# 2024-ZT-2.net
KiCad netlist of a schematic drawn in EasyEDA Pro
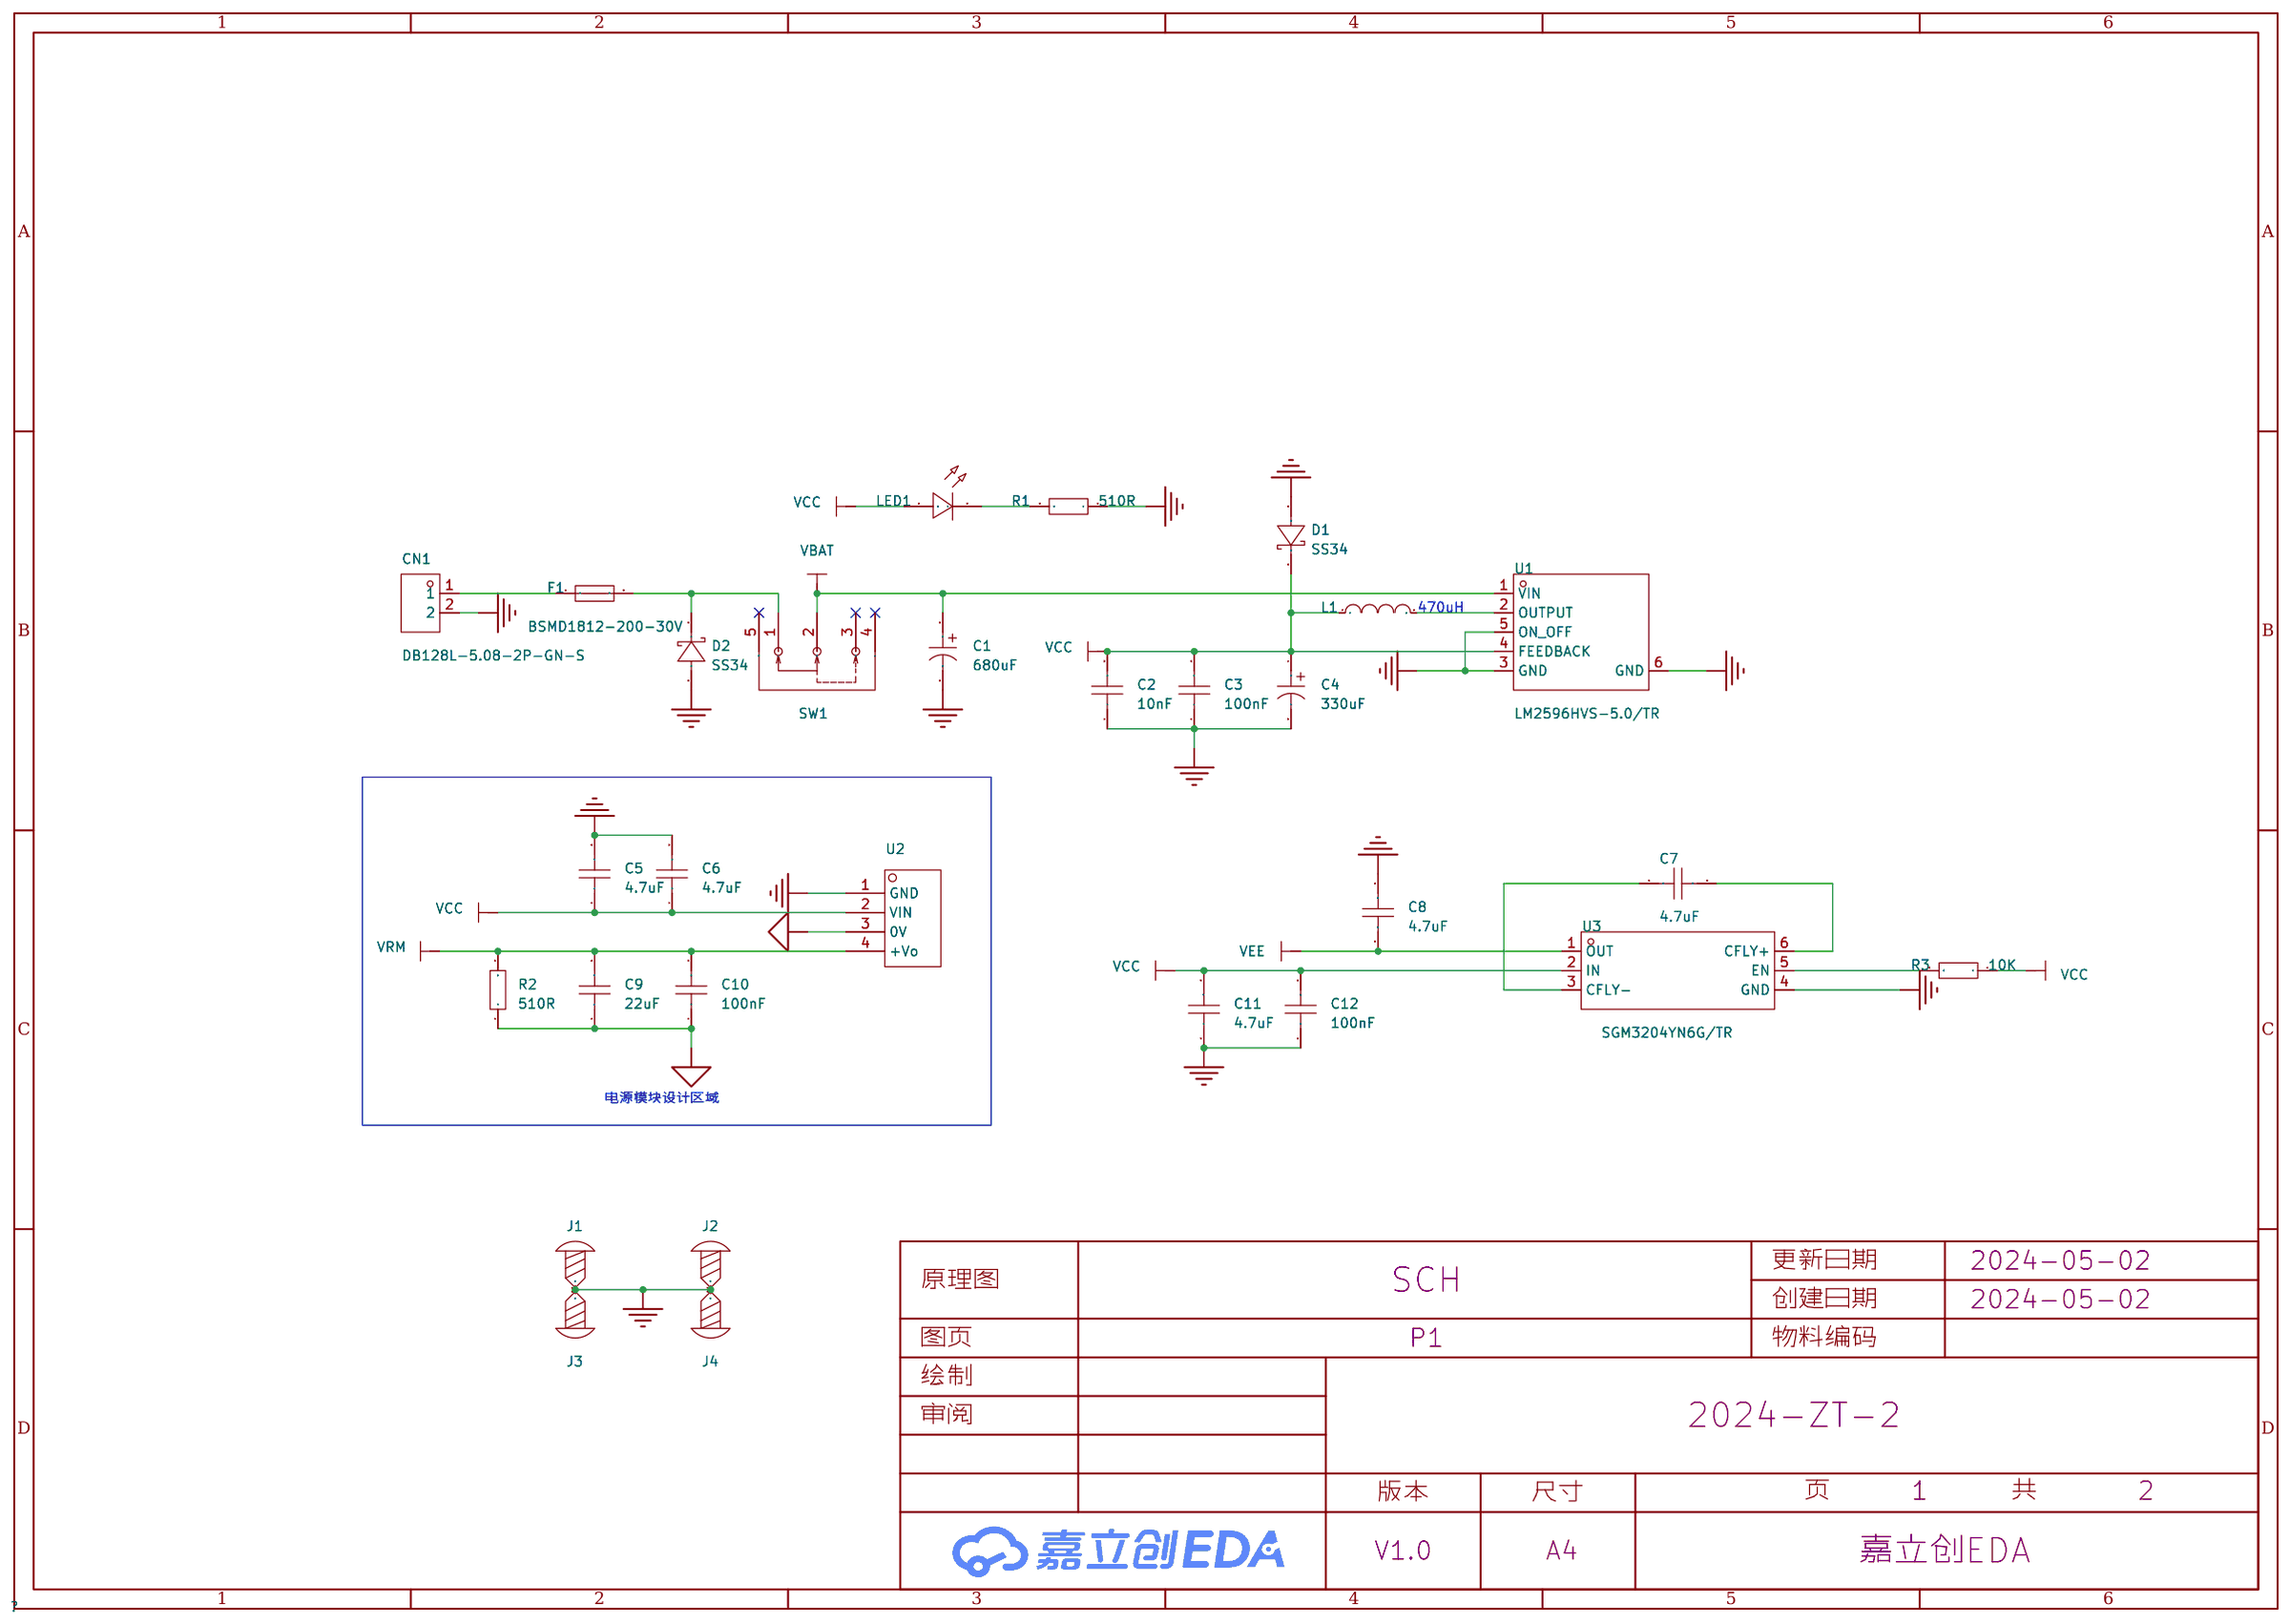
[diagram p0: P1]
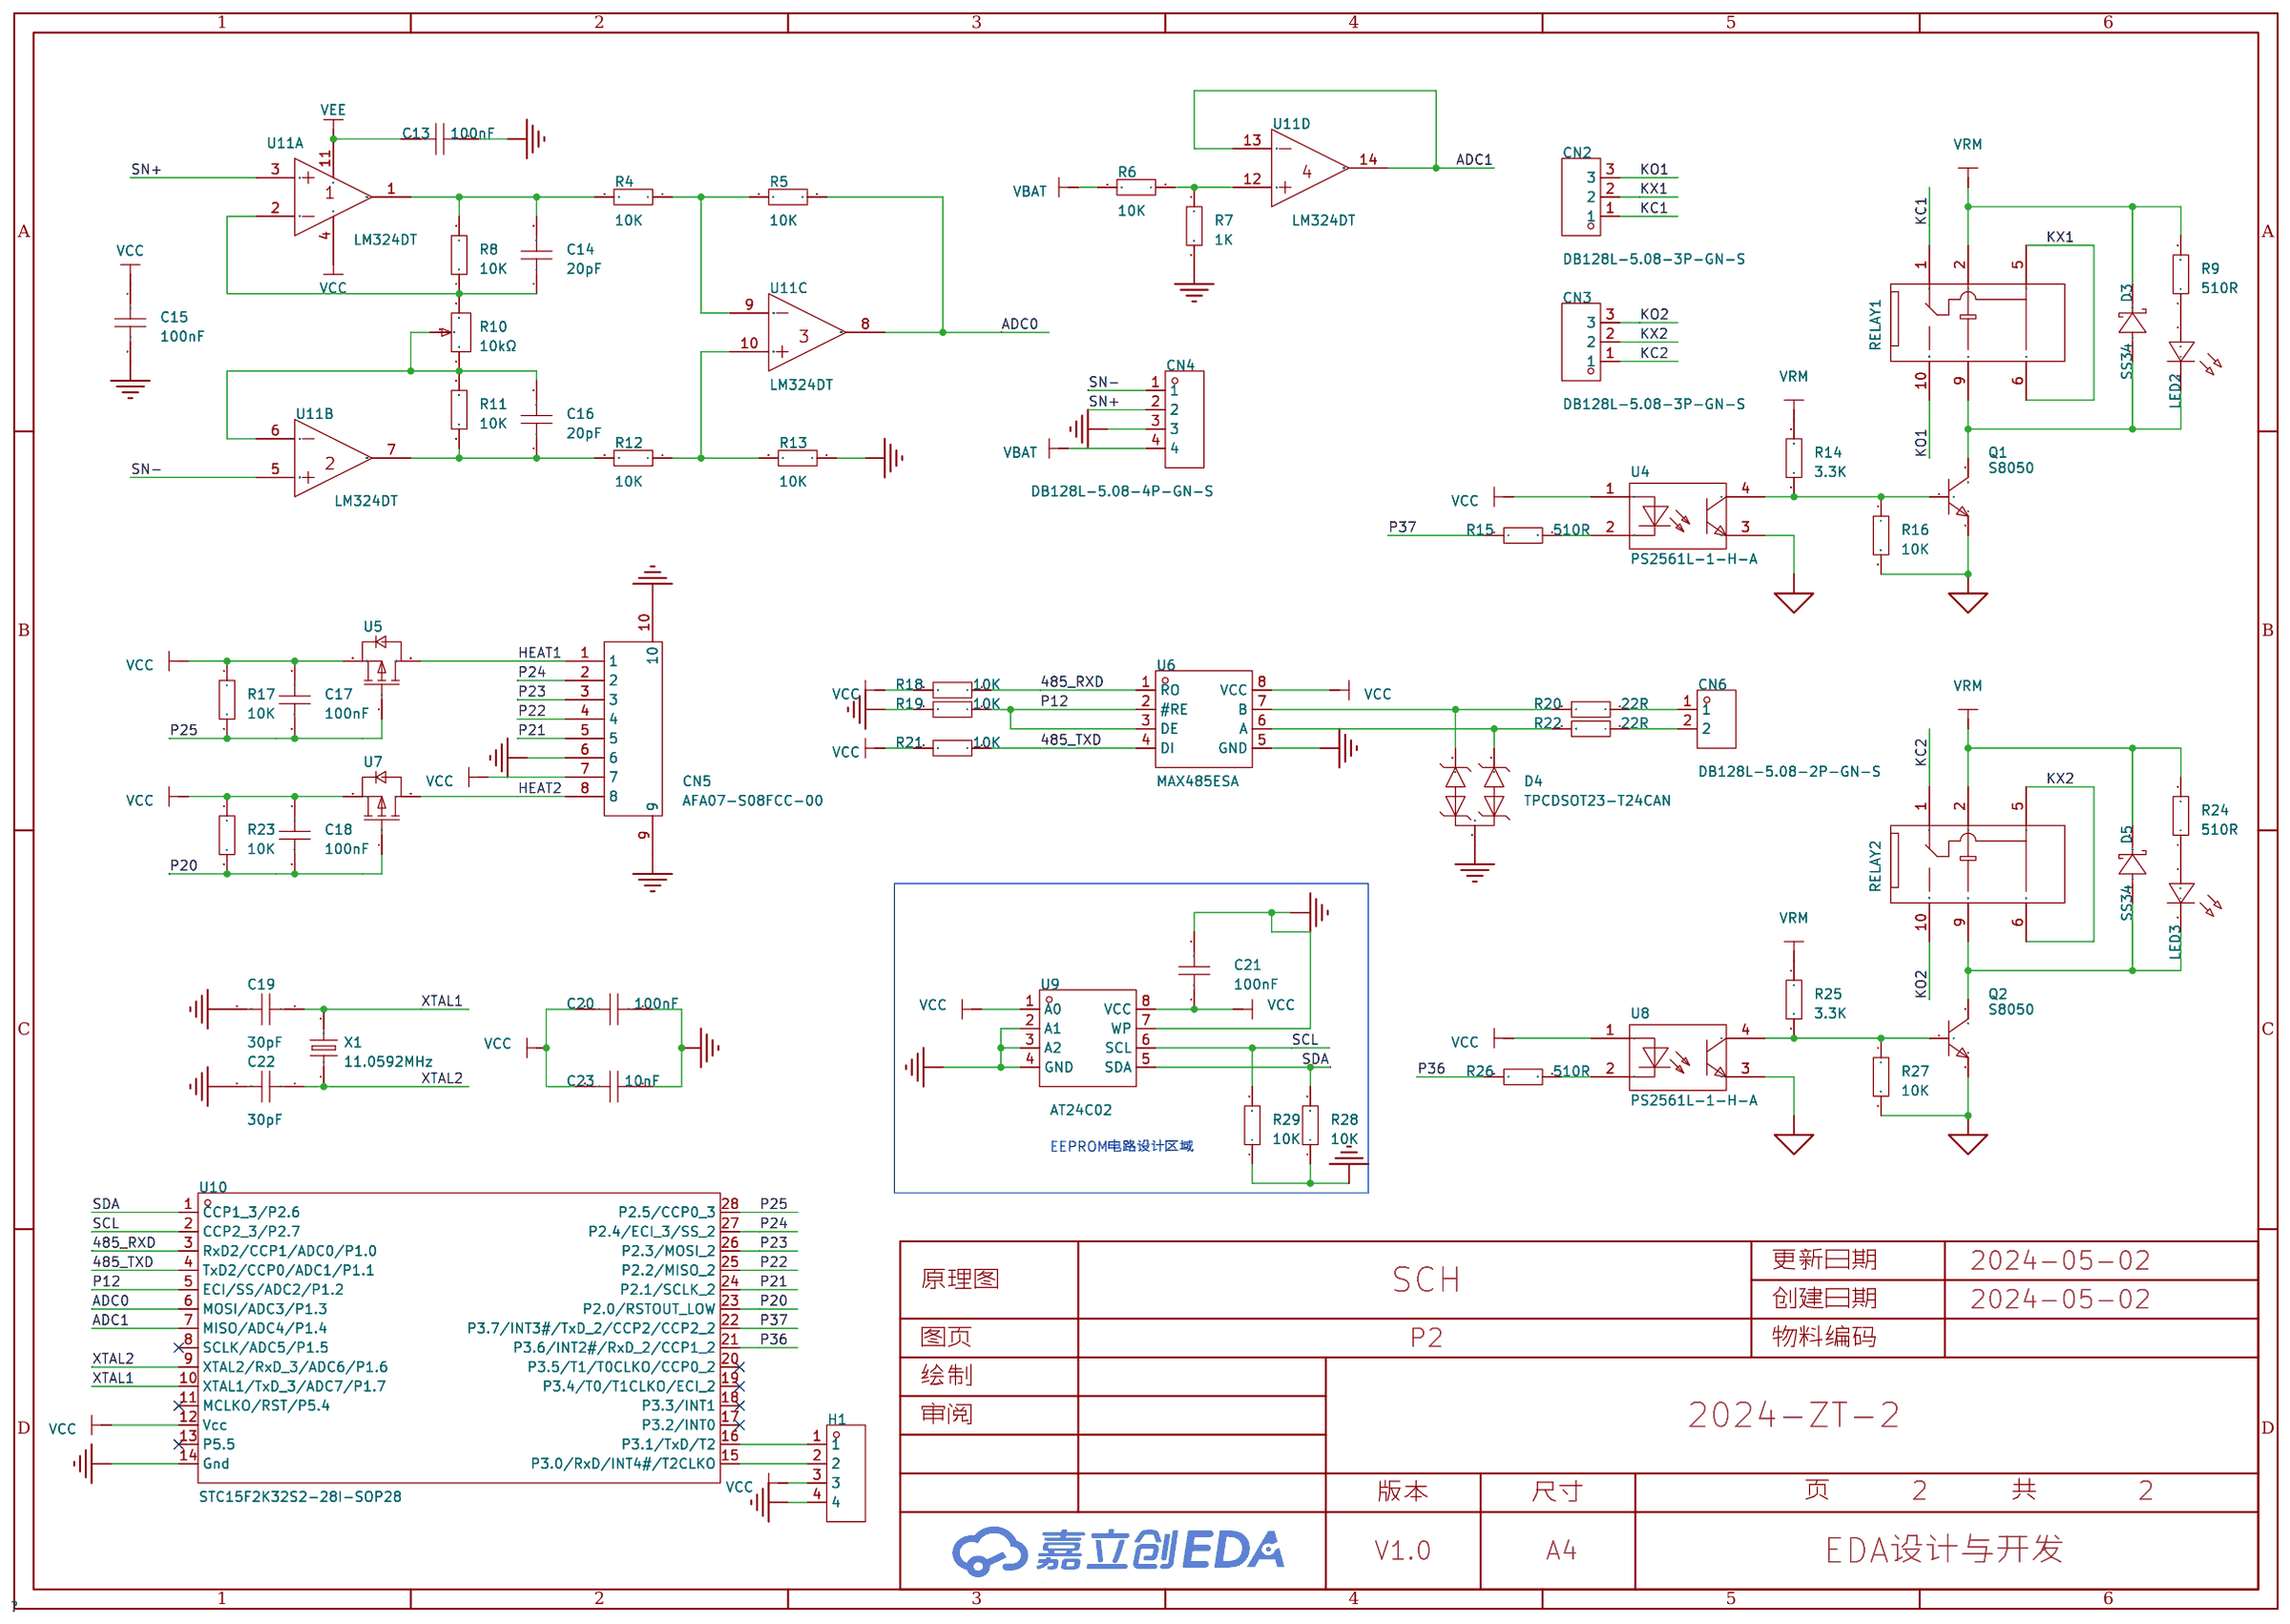
[diagram p1: P2]

(export (version "E")
  (design (tool "Eeschema 10.0.6"))
  (components
    (comp (ref "C1")
      (value "680uF")
      (footprint "easyedapro:CAP-SMD_BD10.0-L10.3-W10.3-LS11.3-FD")
      (description "容值:680uF;精度:±20%;额定电压:35V;纹波电流:380mA;")
      (fields (field (name "Manufacturer Part") "126RV0105") (field (name "Manufacturer") "KNSCHA(科尼盛)"))
      (libsource (lib "easyedapro") (part "126RV0105"))
    )
    (comp (ref "C2")
      (value "10nF")
      (footprint "easyedapro:C0805")
      (libsource (lib "easyedapro") (part "CapAcitance"))
    )
    (comp (ref "C3")
      (value "100nF")
      (footprint "easyedapro:C0805")
      (libsource (lib "easyedapro") (part "CapAcitance"))
    )
    (comp (ref "C4")
      (value "330uF")
      (footprint "easyedapro:CAP-SMD_BD6.3-L6.6-W6.6-LS7.6-RD")
      (description "容值:330uF;精度:±20%;额定电压:16V;纹波电流:170mA;")
      (fields (field (name "Manufacturer Part") "126RV0107") (field (name "Manufacturer") "KNSCHA(科尼盛)"))
      (libsource (lib "easyedapro") (part "126RV0107"))
    )
    (comp (ref "C5")
      (value "4.7uF")
      (footprint "easyedapro:C1206")
      (description "容值:22uF;精度:±10%;额定电压:16V;材质(温度系数):X5R;")
      (fields
        (field (name "Manufacturer Part") "CL31A226KOHNNNE")
        (field (name "Manufacturer") "SAMSUNG(三星)")
      )
      (libsource (lib "easyedapro") (part "CL31A226KOHNNNE"))
    )
    (comp (ref "C6")
      (value "4.7uF")
      (footprint "easyedapro:C1206")
      (description "容值:22uF;精度:±10%;额定电压:16V;材质(温度系数):X5R;")
      (fields
        (field (name "Manufacturer Part") "CL31A226KOHNNNE")
        (field (name "Manufacturer") "SAMSUNG(三星)")
      )
      (libsource (lib "easyedapro") (part "CL31A226KOHNNNE"))
    )
    (comp (ref "C7")
      (value "4.7uF")
      (footprint "easyedapro:C1206")
      (description "容值:22uF;精度:±10%;额定电压:16V;材质(温度系数):X5R;")
      (fields
        (field (name "Manufacturer Part") "CL31A226KOHNNNE")
        (field (name "Manufacturer") "SAMSUNG(三星)")
      )
      (libsource (lib "easyedapro") (part "CL31A226KOHNNNE"))
    )
    (comp (ref "C8")
      (value "4.7uF")
      (footprint "easyedapro:C1206")
      (description "容值:22uF;精度:±10%;额定电压:16V;材质(温度系数):X5R;")
      (fields
        (field (name "Manufacturer Part") "CL31A226KOHNNNE")
        (field (name "Manufacturer") "SAMSUNG(三星)")
      )
      (libsource (lib "easyedapro") (part "CL31A226KOHNNNE"))
    )
    (comp (ref "C9")
      (value "22uF")
      (footprint "easyedapro:C1206")
      (description "容值:22uF;精度:±10%;额定电压:16V;材质(温度系数):X5R;")
      (fields
        (field (name "Manufacturer Part") "CL31A226KOHNNNE")
        (field (name "Manufacturer") "SAMSUNG(三星)")
      )
      (libsource (lib "easyedapro") (part "CL31A226KOHNNNE"))
    )
    (comp (ref "C10")
      (value "100nF")
      (footprint "easyedapro:C0805")
      (libsource (lib "easyedapro") (part "CapAcitance"))
    )
    (comp (ref "C11")
      (value "4.7uF")
      (footprint "easyedapro:C1206")
      (description "容值:22uF;精度:±10%;额定电压:16V;材质(温度系数):X5R;")
      (fields
        (field (name "Manufacturer Part") "CL31A226KOHNNNE")
        (field (name "Manufacturer") "SAMSUNG(三星)")
      )
      (libsource (lib "easyedapro") (part "CL31A226KOHNNNE"))
    )
    (comp (ref "C12")
      (value "100nF")
      (footprint "easyedapro:C0805")
      (libsource (lib "easyedapro") (part "CapAcitance"))
    )
    (comp (ref "CN1")
      (value "DB128L-5.08-2P-GN-S")
      (footprint "easyedapro:CONN-TH_2P-P5.08_DB128L-5.08-2P")
      (fields (field (name "Manufacturer") "DORABO(地博电气)"))
      (libsource (lib "easyedapro") (part "DB128L-5.08-2P"))
    )
    (comp (ref "D1")
      (value "SS34")
      (footprint "easyedapro:SMA_L4.3-W2.5-LS5.0-RD")
      (description "二极管配置:独立式;正向压降(Vf):550mV@3A;直流反向耐压(Vr):40V;平均整流电流(Io):3A;")
      (fields (field (name "Manufacturer") "TWGMC(台湾迪嘉)"))
      (libsource (lib "easyedapro") (part "SS34_C727060"))
    )
    (comp (ref "D2")
      (value "SS34")
      (footprint "easyedapro:SMA_L4.3-W2.5-LS5.0-RD")
      (description "二极管配置:独立式;正向压降(Vf):550mV@3A;直流反向耐压(Vr):40V;平均整流电流(Io):3A;")
      (fields (field (name "Manufacturer") "TWGMC(台湾迪嘉)"))
      (libsource (lib "easyedapro") (part "SS34_C727060"))
    )
    (comp (ref "F1")
      (value "BSMD1812-200-30V")
      (footprint "easyedapro:F1812")
      (description "最大电压:30V;最大电流:40A;保持电流:2A;跳闸电流:4A;")
      (fields (field (name "Manufacturer") "BHFUSE(佰宏)"))
      (libsource (lib "easyedapro") (part "BSMD1812-200-30V"))
    )
    (comp (ref "J1") (value "~") (footprint "easyedapro:M2螺丝") (libsource (lib "easyedapro") (part "螺丝孔")))
    (comp (ref "J2") (value "~") (footprint "easyedapro:M2螺丝") (libsource (lib "easyedapro") (part "螺丝孔")))
    (comp (ref "J3") (value "~") (footprint "easyedapro:M2螺丝") (libsource (lib "easyedapro") (part "螺丝孔")))
    (comp (ref "J4") (value "~") (footprint "easyedapro:M2螺丝") (libsource (lib "easyedapro") (part "螺丝孔")))
    (comp (ref "L1")
      (value "470uH")
      (footprint "easyedapro:IND-SMD_L12.0-W12.0_YPRH120X")
      (description "电感值:470uH;精度:±20%;额定电流:1.06A;")
      (fields (field (name "Manufacturer Part") "YPRH1209-471M") (field (name "Manufacturer") "YJYCOIN(益嘉源)"))
      (libsource (lib "easyedapro") (part "YPRH1209-471M"))
    )
    (comp (ref "LED1")
      (value "~")
      (footprint "easyedapro:LED_TH-3mm")
      (libsource (lib "easyedapro") (part "LED_TH-R"))
    )
    (comp (ref "R1") (value "510R") (footprint "easyedapro:R0805") (libsource (lib "easyedapro") (part "电阻")))
    (comp (ref "R2") (value "510R") (footprint "easyedapro:R0805") (libsource (lib "easyedapro") (part "电阻")))
    (comp (ref "R3") (value "10K") (footprint "easyedapro:R0805") (libsource (lib "easyedapro") (part "电阻")))
    (comp (ref "SW1")
      (value "SK12D07VG4")
      (footprint "easyedapro:SW-TH_SK12D07VG4")
      (description "电路结构:单刀双掷;安装方式:侧插;额定电流(DC):500mA;额定电压(DC):50V;额定电流(AC):-;额定电压(AC):-;机械寿命:5千次;")
      (fields (field (name "Manufacturer") "SHOU HAN(首韩)"))
      (libsource (lib "easyedapro") (part "SK12D07VG4"))
    )
    (comp (ref "U1")
      (value "LM2596HVS-5.0/TR")
      (footprint "easyedapro:TO-263-5_L10.2-W8.9-P1.70-LS15.2-BR")
      (fields (field (name "Manufacturer") "HGSEMI(华冠)"))
      (libsource (lib "easyedapro") (part "LM2596HVS-5.0/TR"))
    )
    (comp (ref "U2") (value "~") (libsource (lib "easyedapro") (part "PCON")))
    (comp (ref "U3")
      (value "SGM3204YN6G/TR")
      (footprint "easyedapro:SOT-23-6_L2.9-W1.6-P0.95-LS2.8-BR")
      (description "功能类型:-;输入电压:1.4V~5.5V;输出电压:-5.5V~-1.4V;输出电流(最大值):200mA;")
      (fields (field (name "Manufacturer") "SGMICRO(圣邦微)"))
      (libsource (lib "easyedapro") (part "SGM3204YN6G/TR"))
    )
    (comp (ref "C13")
      (value "100nF")
      (footprint "easyedapro:C0805")
      (libsource (lib "easyedapro") (part "CapAcitance"))
    )
    (comp (ref "C14")
      (value "20pF")
      (footprint "easyedapro:C0805")
      (libsource (lib "easyedapro") (part "CapAcitance"))
    )
    (comp (ref "C15")
      (value "100nF")
      (footprint "easyedapro:C0805")
      (libsource (lib "easyedapro") (part "CapAcitance"))
    )
    (comp (ref "C16")
      (value "20pF")
      (footprint "easyedapro:C0805")
      (libsource (lib "easyedapro") (part "CapAcitance"))
    )
    (comp (ref "C17")
      (value "100nF")
      (footprint "easyedapro:C0805")
      (libsource (lib "easyedapro") (part "CapAcitance"))
    )
    (comp (ref "C18")
      (value "100nF")
      (footprint "easyedapro:C0805")
      (libsource (lib "easyedapro") (part "CapAcitance"))
    )
    (comp (ref "C19")
      (value "30pF")
      (footprint "easyedapro:C0805")
      (libsource (lib "easyedapro") (part "CapAcitance"))
    )
    (comp (ref "C20")
      (value "100nF")
      (footprint "easyedapro:C0805")
      (libsource (lib "easyedapro") (part "CapAcitance"))
    )
    (comp (ref "C21")
      (value "100nF")
      (footprint "easyedapro:C0805")
      (libsource (lib "easyedapro") (part "CapAcitance"))
    )
    (comp (ref "C22")
      (value "30pF")
      (footprint "easyedapro:C0805")
      (libsource (lib "easyedapro") (part "CapAcitance"))
    )
    (comp (ref "C23")
      (value "10nF")
      (footprint "easyedapro:C0805")
      (libsource (lib "easyedapro") (part "CapAcitance"))
    )
    (comp (ref "CN2")
      (value "DB128L-5.08-3P-GN-S")
      (footprint "easyedapro:CONN-TH_DB128L-5.08-3P")
      (fields (field (name "Manufacturer") "DORABO(地博电气)"))
      (libsource (lib "easyedapro") (part "DB128L-5.08-3P"))
    )
    (comp (ref "CN3")
      (value "DB128L-5.08-3P-GN-S")
      (footprint "easyedapro:CONN-TH_DB128L-5.08-3P")
      (fields (field (name "Manufacturer") "DORABO(地博电气)"))
      (libsource (lib "easyedapro") (part "DB128L-5.08-3P"))
    )
    (comp (ref "CN4")
      (value "DB128L-5.08-4P-GN-S")
      (footprint "easyedapro:CONN-TH_4P_DB128L-5.08-4P-GN-S")
      (fields (field (name "Manufacturer") "DORABO(地博电气)"))
      (libsource (lib "easyedapro") (part "DB128L-5.08-4P-GN-S"))
    )
    (comp (ref "CN5")
      (value "AFA07-S08FCC-00")
      (footprint "easyedapro:FPC-SMD_P1.00-8P_LCS-XJ-H2.5")
      (description "锁定特性:抽屉式;触点类型:下接;触点数量:8P;间距:1mm;安装类型:卧贴;")
      (fields (field (name "Manufacturer") "JS(钜硕电子)"))
      (libsource (lib "easyedapro") (part "AFA07-S08FCC-00"))
    )
    (comp (ref "CN6")
      (value "DB128L-5.08-2P-GN-S")
      (footprint "easyedapro:CONN-TH_2P-P5.08_DB128L-5.08-2P")
      (fields (field (name "Manufacturer") "DORABO(地博电气)"))
      (libsource (lib "easyedapro") (part "DB128L-5.08-2P"))
    )
    (comp (ref "D3")
      (value "SS34")
      (footprint "easyedapro:SMA_L4.3-W2.5-LS5.0-RD")
      (description "二极管配置:独立式;正向压降(Vf):550mV@3A;直流反向耐压(Vr):40V;平均整流电流(Io):3A;")
      (fields (field (name "Manufacturer") "TWGMC(台湾迪嘉)"))
      (libsource (lib "easyedapro") (part "SS34_C727060"))
    )
    (comp (ref "D4")
      (value "TPCDSOT23-T24CAN")
      (footprint "easyedapro:SOT-23-3_L2.9-W1.3-P1.90-LS2.4-BR")
      (fields (field (name "Manufacturer") "TECH PUBLIC(台舟)"))
      (libsource (lib "easyedapro") (part "TPCDSOT23-T24CAN"))
    )
    (comp (ref "D5")
      (value "SS34")
      (footprint "easyedapro:SMA_L4.3-W2.5-LS5.0-RD")
      (description "二极管配置:独立式;正向压降(Vf):550mV@3A;直流反向耐压(Vr):40V;平均整流电流(Io):3A;")
      (fields (field (name "Manufacturer") "TWGMC(台湾迪嘉)"))
      (libsource (lib "easyedapro") (part "SS34_C727060"))
    )
    (comp (ref "H1")
      (value "~")
      (footprint "easyedapro:HDR-TH_4P-P2.54-V-F")
      (libsource (lib "easyedapro") (part "2.54-1*4P母"))
    )
    (comp (ref "LED2")
      (value "~")
      (footprint "easyedapro:LED_TH-3mm")
      (libsource (lib "easyedapro") (part "LED_TH-G"))
    )
    (comp (ref "LED3")
      (value "~")
      (footprint "easyedapro:LED_TH-3mm")
      (libsource (lib "easyedapro") (part "LED_TH-G"))
    )
    (comp (ref "Q1")
      (value "S8050")
      (footprint "easyedapro:SOT-23-3_L2.9-W1.3-P1.90-LS2.4-BR")
      (description "晶体管类型:NPN;集电极电流(Ic):500mA;集射极击穿电压(Vceo):25V;功率(Pd):300mW;")
      (fields (field (name "Manufacturer") "YONGYUTAI(永裕泰)"))
      (libsource (lib "easyedapro") (part "S8050_C2891804"))
    )
    (comp (ref "Q2")
      (value "S8050")
      (footprint "easyedapro:SOT-23-3_L2.9-W1.3-P1.90-LS2.4-BR")
      (description "晶体管类型:NPN;集电极电流(Ic):500mA;集射极击穿电压(Vceo):25V;功率(Pd):300mW;")
      (fields (field (name "Manufacturer") "YONGYUTAI(永裕泰)"))
      (libsource (lib "easyedapro") (part "S8050_C2891804"))
    )
    (comp (ref "R4") (value "10K") (footprint "easyedapro:R0805") (libsource (lib "easyedapro") (part "电阻")))
    (comp (ref "R5") (value "10K") (footprint "easyedapro:R0805") (libsource (lib "easyedapro") (part "电阻")))
    (comp (ref "R6") (value "10K") (footprint "easyedapro:R0805") (libsource (lib "easyedapro") (part "电阻")))
    (comp (ref "R7") (value "1K") (footprint "easyedapro:R0805") (libsource (lib "easyedapro") (part "电阻")))
    (comp (ref "R8") (value "10K") (footprint "easyedapro:R0805") (libsource (lib "easyedapro") (part "电阻")))
    (comp (ref "R9") (value "510R") (footprint "easyedapro:R0805") (libsource (lib "easyedapro") (part "电阻")))
    (comp (ref "R10")
      (value "10kΩ")
      (footprint "easyedapro:RES-ADJ-TH_3P-L10.0-W10.0-P2.50-BL-BS")
      (description "阻值:20kΩ;精度:±10%;功率:500mW;温度系数:±100ppm/°C;")
      (fields (field (name "Manufacturer Part") "3296W-1-203LF") (field (name "Manufacturer") "BOURNS"))
      (libsource (lib "easyedapro") (part "3296W-1-203LF"))
    )
    (comp (ref "R11") (value "10K") (footprint "easyedapro:R0805") (libsource (lib "easyedapro") (part "电阻")))
    (comp (ref "R12") (value "10K") (footprint "easyedapro:R0805") (libsource (lib "easyedapro") (part "电阻")))
    (comp (ref "R13") (value "10K") (footprint "easyedapro:R0805") (libsource (lib "easyedapro") (part "电阻")))
    (comp (ref "R14")
      (value "3.3K")
      (footprint "easyedapro:R0805")
      (libsource (lib "easyedapro") (part "电阻"))
    )
    (comp (ref "R15")
      (value "510R")
      (footprint "easyedapro:R0805")
      (libsource (lib "easyedapro") (part "电阻"))
    )
    (comp (ref "R16") (value "10K") (footprint "easyedapro:R0805") (libsource (lib "easyedapro") (part "电阻")))
    (comp (ref "R17") (value "10K") (footprint "easyedapro:R0805") (libsource (lib "easyedapro") (part "电阻")))
    (comp (ref "R18") (value "10K") (footprint "easyedapro:R0805") (libsource (lib "easyedapro") (part "电阻")))
    (comp (ref "R19") (value "10K") (footprint "easyedapro:R0805") (libsource (lib "easyedapro") (part "电阻")))
    (comp (ref "R20") (value "22R") (footprint "easyedapro:R0805") (libsource (lib "easyedapro") (part "电阻")))
    (comp (ref "R21") (value "10K") (footprint "easyedapro:R0805") (libsource (lib "easyedapro") (part "电阻")))
    (comp (ref "R22") (value "22R") (footprint "easyedapro:R0805") (libsource (lib "easyedapro") (part "电阻")))
    (comp (ref "R23") (value "10K") (footprint "easyedapro:R0805") (libsource (lib "easyedapro") (part "电阻")))
    (comp (ref "R24")
      (value "510R")
      (footprint "easyedapro:R0805")
      (libsource (lib "easyedapro") (part "电阻"))
    )
    (comp (ref "R25")
      (value "3.3K")
      (footprint "easyedapro:R0805")
      (libsource (lib "easyedapro") (part "电阻"))
    )
    (comp (ref "R26")
      (value "510R")
      (footprint "easyedapro:R0805")
      (libsource (lib "easyedapro") (part "电阻"))
    )
    (comp (ref "R27") (value "10K") (footprint "easyedapro:R0805") (libsource (lib "easyedapro") (part "电阻")))
    (comp (ref "R28") (value "10K") (footprint "easyedapro:R0805") (libsource (lib "easyedapro") (part "电阻")))
    (comp (ref "R29") (value "10K") (footprint "easyedapro:R0805") (libsource (lib "easyedapro") (part "电阻")))
    (comp (ref "RELAY1")
      (value "G5V-1 DC5")
      (footprint "easyedapro:RELAY-TH_G5V-1")
      (description "线圈电压:5V;触点形式:一组转换:1C(单刀双掷-转换);触点容量(电阻负载):-;最大切换电压:125V@AC；60V@DC;最大切换电流:1A;")
      (fields (field (name "Manufacturer") "OMRON(欧姆龙)"))
      (libsource (lib "easyedapro") (part "G5V-1-5VDC"))
    )
    (comp (ref "RELAY2")
      (value "G5V-1 DC5")
      (footprint "easyedapro:RELAY-TH_G5V-1")
      (description "线圈电压:5V;触点形式:一组转换:1C(单刀双掷-转换);触点容量(电阻负载):-;最大切换电压:125V@AC；60V@DC;最大切换电流:1A;")
      (fields (field (name "Manufacturer") "OMRON(欧姆龙)"))
      (libsource (lib "easyedapro") (part "G5V-1-5VDC"))
    )
    (comp (ref "U4")
      (value "PS2561L-1-H-A")
      (footprint "easyedapro:SOP-4_L6.5-W4.6-P2.54-LS9.6-TL")
      (fields (field (name "Manufacturer") "California Eastern Laboratories"))
      (libsource (lib "easyedapro") (part "PS2561L-1-H-A"))
    )
    (comp (ref "U5")
      (value "SI2301-ZE")
      (footprint "easyedapro:SOT-23-3_L2.9-W1.3-P1.90-LS2.4-BR")
      (fields (field (name "Manufacturer") "HXY MOSFET(华轩阳电子)"))
      (libsource (lib "easyedapro") (part "SI2301-ZE"))
    )
    (comp (ref "U6")
      (value "MAX485ESA")
      (footprint "easyedapro:SOP-8_L5.0-W4.0-P1.27-LS6.0-BL")
      (fields (field (name "Manufacturer") "UMW(友台半导体)"))
      (libsource (lib "easyedapro") (part "MAX485EAS"))
    )
    (comp (ref "U7")
      (value "SI2301-ZE")
      (footprint "easyedapro:SOT-23-3_L2.9-W1.3-P1.90-LS2.4-BR")
      (fields (field (name "Manufacturer") "HXY MOSFET(华轩阳电子)"))
      (libsource (lib "easyedapro") (part "SI2301-ZE"))
    )
    (comp (ref "U8")
      (value "PS2561L-1-H-A")
      (footprint "easyedapro:SOP-4_L6.5-W4.6-P2.54-LS9.6-TL")
      (fields (field (name "Manufacturer") "California Eastern Laboratories"))
      (libsource (lib "easyedapro") (part "PS2561L-1-H-A"))
    )
    (comp (ref "U9")
      (value "AT24C02")
      (footprint "easyedapro:SOP-8_L4.9-W3.9-P1.27-LS6.0-BL")
      (description "接口类型:I2C;存储容量:2Kbit;时钟频率(fc):400kHz~1MHz;")
      (fields (field (name "Manufacturer") "HXY MOSFET(华轩阳电子)"))
      (libsource (lib "easyedapro") (part "AT24C02_C7470930"))
    )
    (comp (ref "U10")
      (value "STC15F2K32S2-28I-SOP28")
      (footprint "easyedapro:SOP-28_L17.9-W7.5-P1.27-LS10.3-BL")
      (fields (field (name "Manufacturer") "STC(宏晶)"))
      (libsource (lib "easyedapro") (part "STC15F2K32S2-28I-SOP28"))
    )
    (comp (ref "U11")
      (value "LM324DT")
      (footprint "easyedapro:SOIC-14_L8.7-W3.9-P1.27-LS6.0-BL")
      (description "放大器数:四路;增益带宽积(GBP):1.3MHz;输入偏置电流(Ib):20nA;压摆率(SR):0.4V/us;带宽(-3db):-;")
      (fields (field (name "Manufacturer") "ST(意法半导体)"))
      (libsource (lib "easyedapro") (part "LM324DT"))
    )
    (comp (ref "X1")
      (value "11.0592MHz")
      (footprint "easyedapro:HC-49US_L11.5-W4.5-P4.88")
      (description "晶振类型:直插晶振;频率:11.0592MHz;常温频差:±30ppm;外接负载电容:20pF;频率稳定度(全温):±30ppm;")
      (fields
        (field (name "Manufacturer Part") "TAXD11.0592M2GLFBET2T")
        (field (name "Manufacturer") "YJX(雅晶鑫)")
      )
      (libsource (lib "easyedapro") (part "HC-49S11.0592MHZ20PF30PPM"))
    )
  )
  (nets
    (net (code "1") (name "0") (class "Default")
      (node (ref "C10") (pin "1") (pinfunction "1_1") (pintype "input"))
      (node (ref "C9") (pin "1") (pinfunction "1_1") (pintype "unspecified"))
      (node (ref "Q1") (pin "2") (pinfunction "E_2") (pintype "unspecified"))
      (node (ref "Q2") (pin "2") (pinfunction "E_2") (pintype "unspecified"))
      (node (ref "R16") (pin "2") (pinfunction "2_2") (pintype "input"))
      (node (ref "R2") (pin "1") (pinfunction "1_1") (pintype "input"))
      (node (ref "R27") (pin "2") (pinfunction "2_2") (pintype "input"))
      (node (ref "U2") (pin "3") (pinfunction "0V_3") (pintype "input"))
      (node (ref "U4") (pin "3") (pinfunction "3_3") (pintype "input"))
      (node (ref "U8") (pin "3") (pinfunction "3_3") (pintype "input"))
    )
    (net (code "2") (name "485_RXD") (class "Default")
      (node (ref "R18") (pin "1") (pinfunction "1_1") (pintype "input"))
      (node (ref "U10") (pin "3") (pinfunction "RxD2/CCP1/ADC0/P1.0_3") (pintype "input"))
      (node (ref "U6") (pin "1") (pinfunction "RO_1") (pintype "unspecified"))
    )
    (net (code "3") (name "485_TXD") (class "Default")
      (node (ref "R21") (pin "1") (pinfunction "1_1") (pintype "input"))
      (node (ref "U10") (pin "4") (pinfunction "TxD2/CCP0/ADC1/P1.1_4") (pintype "input"))
      (node (ref "U6") (pin "4") (pinfunction "DI_4") (pintype "unspecified"))
    )
    (net (code "4") (name "ADC0") (class "Default")
      (node (ref "R5") (pin "1") (pinfunction "1_1") (pintype "input"))
      (node (ref "U10") (pin "6") (pinfunction "MOSI/ADC3/P1.3_6") (pintype "input"))
      (node (ref "U11") (pin "8") (pinfunction "OUT3_8") (pintype "unspecified"))
    )
    (net (code "5") (name "ADC1") (class "Default")
      (node (ref "U10") (pin "7") (pinfunction "MISO/ADC4/P1.4_7") (pintype "input"))
      (node (ref "U11") (pin "13") (pinfunction "IN4-_13") (pintype "unspecified"))
      (node (ref "U11") (pin "14") (pinfunction "OUT4_14") (pintype "unspecified"))
    )
    (net (code "6") (name "GND") (class "Default")
      (node (ref "C1") (pin "2") (pinfunction "2_2") (pintype "input"))
      (node (ref "C11") (pin "1") (pinfunction "1_1") (pintype "unspecified"))
      (node (ref "C12") (pin "1") (pinfunction "1_1") (pintype "input"))
      (node (ref "C13") (pin "1") (pinfunction "1_1") (pintype "input"))
      (node (ref "C15") (pin "2") (pinfunction "2_2") (pintype "input"))
      (node (ref "C19") (pin "2") (pinfunction "2_2") (pintype "input"))
      (node (ref "C2") (pin "1") (pinfunction "1_1") (pintype "input"))
      (node (ref "C20") (pin "1") (pinfunction "1_1") (pintype "input"))
      (node (ref "C21") (pin "2") (pinfunction "2_2") (pintype "input"))
      (node (ref "C22") (pin "2") (pinfunction "2_2") (pintype "input"))
      (node (ref "C23") (pin "1") (pinfunction "1_1") (pintype "input"))
      (node (ref "C3") (pin "1") (pinfunction "1_1") (pintype "input"))
      (node (ref "C4") (pin "2") (pinfunction "2_2") (pintype "input"))
      (node (ref "C5") (pin "2") (pinfunction "2_2") (pintype "unspecified"))
      (node (ref "C6") (pin "2") (pinfunction "2_2") (pintype "unspecified"))
      (node (ref "C8") (pin "1") (pinfunction "1_1") (pintype "unspecified"))
      (node (ref "CN1") (pin "2") (pinfunction "2_2") (pintype "unspecified"))
      (node (ref "CN4") (pin "3") (pinfunction "3_3") (pintype "unspecified"))
      (node (ref "CN5") (pin "10") (pinfunction "10_10") (pintype "unspecified"))
      (node (ref "CN5") (pin "6") (pinfunction "6_6") (pintype "unspecified"))
      (node (ref "CN5") (pin "9") (pinfunction "9_9") (pintype "unspecified"))
      (node (ref "D1") (pin "2") (pinfunction "A_2") (pintype "unspecified"))
      (node (ref "D2") (pin "2") (pinfunction "A_2") (pintype "unspecified"))
      (node (ref "D4") (pin "3") (pinfunction "3_3") (pintype "unspecified"))
      (node (ref "H1") (pin "4") (pinfunction "4_4") (pintype "unspecified"))
      (node (ref "J1") (pin "1") (pinfunction "1_1") (pintype "input"))
      (node (ref "J2") (pin "1") (pinfunction "1_1") (pintype "input"))
      (node (ref "J3") (pin "1") (pinfunction "1_1") (pintype "input"))
      (node (ref "J4") (pin "1") (pinfunction "1_1") (pintype "input"))
      (node (ref "R1") (pin "1") (pinfunction "1_1") (pintype "input"))
      (node (ref "R13") (pin "1") (pinfunction "1_1") (pintype "input"))
      (node (ref "R19") (pin "2") (pinfunction "2_2") (pintype "input"))
      (node (ref "R28") (pin "1") (pinfunction "1_1") (pintype "input"))
      (node (ref "R29") (pin "1") (pinfunction "1_1") (pintype "input"))
      (node (ref "R7") (pin "2") (pinfunction "2_2") (pintype "input"))
      (node (ref "U1") (pin "3") (pinfunction "GND_3") (pintype "input"))
      (node (ref "U1") (pin "5") (pinfunction "ON_OFF_5") (pintype "input"))
      (node (ref "U1") (pin "6") (pinfunction "GND_6") (pintype "input"))
      (node (ref "U10") (pin "14") (pinfunction "Gnd_14") (pintype "input"))
      (node (ref "U2") (pin "1") (pinfunction "GND_1") (pintype "input"))
      (node (ref "U3") (pin "4") (pinfunction "GND_4") (pintype "unspecified"))
      (node (ref "U6") (pin "5") (pinfunction "GND_5") (pintype "unspecified"))
      (node (ref "U9") (pin "2") (pinfunction "A1_2") (pintype "unspecified"))
      (node (ref "U9") (pin "3") (pinfunction "A2_3") (pintype "unspecified"))
      (node (ref "U9") (pin "4") (pinfunction "GND_4") (pintype "unspecified"))
      (node (ref "U9") (pin "7") (pinfunction "WP_7") (pintype "unspecified"))
    )
    (net (code "7") (name "HEAT1") (class "Default")
      (node (ref "CN5") (pin "1") (pinfunction "1_1") (pintype "unspecified"))
      (node (ref "U5") (pin "3") (pinfunction "D_3") (pintype "unspecified"))
    )
    (net (code "8") (name "HEAT2") (class "Default")
      (node (ref "CN5") (pin "8") (pinfunction "8_8") (pintype "unspecified"))
      (node (ref "U7") (pin "3") (pinfunction "D_3") (pintype "unspecified"))
    )
    (net (code "9") (name "KC1") (class "Default")
      (node (ref "CN2") (pin "1") (pinfunction "1_1") (pintype "unspecified"))
      (node (ref "RELAY1") (pin "1") (pinfunction "1_1") (pintype "input"))
    )
    (net (code "10") (name "KC2") (class "Default")
      (node (ref "CN3") (pin "1") (pinfunction "1_1") (pintype "unspecified"))
      (node (ref "RELAY2") (pin "1") (pinfunction "1_1") (pintype "input"))
    )
    (net (code "11") (name "KO1") (class "Default")
      (node (ref "CN2") (pin "3") (pinfunction "3_3") (pintype "unspecified"))
      (node (ref "RELAY1") (pin "10") (pinfunction "10_10") (pintype "input"))
    )
    (net (code "12") (name "KO2") (class "Default")
      (node (ref "CN3") (pin "3") (pinfunction "3_3") (pintype "unspecified"))
      (node (ref "RELAY2") (pin "10") (pinfunction "10_10") (pintype "input"))
    )
    (net (code "13") (name "KX1") (class "Default")
      (node (ref "CN2") (pin "2") (pinfunction "2_2") (pintype "unspecified"))
      (node (ref "RELAY1") (pin "5") (pinfunction "5_5") (pintype "input"))
      (node (ref "RELAY1") (pin "6") (pinfunction "6_6") (pintype "input"))
    )
    (net (code "14") (name "KX2") (class "Default")
      (node (ref "CN3") (pin "2") (pinfunction "2_2") (pintype "unspecified"))
      (node (ref "RELAY2") (pin "5") (pinfunction "5_5") (pintype "input"))
      (node (ref "RELAY2") (pin "6") (pinfunction "6_6") (pintype "input"))
    )
    (net (code "15") (name "Net-(CN1-Pad1)") (class "Default")
      (node (ref "CN1") (pin "1") (pinfunction "1_1") (pintype "unspecified"))
      (node (ref "F1") (pin "1") (pinfunction "1_1") (pintype "unspecified"))
    )
    (net (code "16") (name "Net-(CN6-Pad1)") (class "Default")
      (node (ref "CN6") (pin "1") (pinfunction "1_1") (pintype "unspecified"))
      (node (ref "R20") (pin "1") (pinfunction "1_1") (pintype "input"))
    )
    (net (code "17") (name "Net-(CN6-Pad2)") (class "Default")
      (node (ref "CN6") (pin "2") (pinfunction "2_2") (pintype "unspecified"))
      (node (ref "R22") (pin "1") (pinfunction "1_1") (pintype "input"))
    )
    (net (code "18") (name "Net-(D2-C)") (class "Default")
      (node (ref "D2") (pin "1") (pinfunction "C_1") (pintype "unspecified"))
      (node (ref "F1") (pin "2") (pinfunction "2_2") (pintype "unspecified"))
      (node (ref "SW1") (pin "1") (pinfunction "1_1") (pintype "unspecified"))
    )
    (net (code "19") (name "Net-(D3-A)") (class "Default")
      (node (ref "D3") (pin "2") (pinfunction "A_2") (pintype "unspecified"))
      (node (ref "LED2") (pin "2") (pinfunction "A_2") (pintype "input"))
      (node (ref "Q1") (pin "3") (pinfunction "C_3") (pintype "unspecified"))
      (node (ref "RELAY1") (pin "9") (pinfunction "9_9") (pintype "input"))
    )
    (net (code "20") (name "Net-(D5-A)") (class "Default")
      (node (ref "D5") (pin "2") (pinfunction "A_2") (pintype "unspecified"))
      (node (ref "LED3") (pin "2") (pinfunction "A_2") (pintype "input"))
      (node (ref "Q2") (pin "3") (pinfunction "C_3") (pintype "unspecified"))
      (node (ref "RELAY2") (pin "9") (pinfunction "9_9") (pintype "input"))
    )
    (net (code "21") (name "Net-(LED1-A)") (class "Default")
      (node (ref "LED1") (pin "2") (pinfunction "A_2") (pintype "input"))
      (node (ref "R1") (pin "2") (pinfunction "2_2") (pintype "input"))
    )
    (net (code "22") (name "Net-(LED2-C)") (class "Default")
      (node (ref "LED2") (pin "1") (pinfunction "C_1") (pintype "input"))
      (node (ref "R9") (pin "1") (pinfunction "1_1") (pintype "input"))
    )
    (net (code "23") (name "Net-(LED3-C)") (class "Default")
      (node (ref "LED3") (pin "1") (pinfunction "C_1") (pintype "input"))
      (node (ref "R24") (pin "1") (pinfunction "1_1") (pintype "input"))
    )
    (net (code "24") (name "Net-(Q1-B)") (class "Default")
      (node (ref "Q1") (pin "1") (pinfunction "B_1") (pintype "unspecified"))
      (node (ref "R14") (pin "2") (pinfunction "2_2") (pintype "input"))
      (node (ref "R16") (pin "1") (pinfunction "1_1") (pintype "input"))
      (node (ref "U4") (pin "4") (pinfunction "4_4") (pintype "input"))
    )
    (net (code "25") (name "Net-(Q2-B)") (class "Default")
      (node (ref "Q2") (pin "1") (pinfunction "B_1") (pintype "unspecified"))
      (node (ref "R25") (pin "2") (pinfunction "2_2") (pintype "input"))
      (node (ref "R27") (pin "1") (pinfunction "1_1") (pintype "input"))
      (node (ref "U8") (pin "4") (pinfunction "4_4") (pintype "input"))
    )
    (net (code "26") (name "Net-(R15-Pad2)") (class "Default")
      (node (ref "R15") (pin "2") (pinfunction "2_2") (pintype "input"))
      (node (ref "U4") (pin "2") (pinfunction "2_2") (pintype "input"))
    )
    (net (code "27") (name "Net-(R26-Pad2)") (class "Default")
      (node (ref "R26") (pin "2") (pinfunction "2_2") (pintype "input"))
      (node (ref "U8") (pin "2") (pinfunction "2_2") (pintype "input"))
    )
    (net (code "28") (name "Net-(U1-OUTPUT)") (class "Default")
      (node (ref "L1") (pin "2") (pinfunction "2_2") (pintype "unspecified"))
      (node (ref "U1") (pin "2") (pinfunction "OUTPUT_2") (pintype "input"))
    )
    (net (code "29") (name "Net-(U3-CFLY+)") (class "Default")
      (node (ref "C7") (pin "2") (pinfunction "2_2") (pintype "unspecified"))
      (node (ref "U3") (pin "6") (pinfunction "CFLY+_6") (pintype "unspecified"))
    )
    (net (code "30") (name "Net-(U3-CFLY-)") (class "Default")
      (node (ref "C7") (pin "1") (pinfunction "1_1") (pintype "unspecified"))
      (node (ref "U3") (pin "3") (pinfunction "CFLY-_3") (pintype "unspecified"))
    )
    (net (code "31") (name "Net-(U3-EN)") (class "Default")
      (node (ref "R3") (pin "2") (pinfunction "2_2") (pintype "input"))
      (node (ref "U3") (pin "5") (pinfunction "EN_5") (pintype "unspecified"))
    )
    (net (code "32") (name "Net-(U6-A)") (class "Default")
      (node (ref "D4") (pin "1") (pinfunction "1_1") (pintype "unspecified"))
      (node (ref "R22") (pin "2") (pinfunction "2_2") (pintype "input"))
      (node (ref "U6") (pin "6") (pinfunction "A_6") (pintype "unspecified"))
    )
    (net (code "33") (name "Net-(U6-B)") (class "Default")
      (node (ref "D4") (pin "2") (pinfunction "2_2") (pintype "unspecified"))
      (node (ref "R20") (pin "2") (pinfunction "2_2") (pintype "input"))
      (node (ref "U6") (pin "7") (pinfunction "B_7") (pintype "unspecified"))
    )
    (net (code "34") (name "Net-(U10-P3.0{slash}RxD{slash}INT4#{slash}T2CLKO)") (class "Default")
      (node (ref "H1") (pin "2") (pinfunction "2_2") (pintype "unspecified"))
      (node (ref "U10") (pin "15") (pinfunction "P3.0/RxD/INT4#/T2CLKO_15") (pintype "input"))
    )
    (net (code "35") (name "Net-(U10-P3.1{slash}TxD{slash}T2)") (class "Default")
      (node (ref "H1") (pin "1") (pinfunction "1_1") (pintype "unspecified"))
      (node (ref "U10") (pin "16") (pinfunction "P3.1/TxD/T2_16") (pintype "input"))
    )
    (net (code "36") (name "Net-(U11A-IN1-)") (class "Default")
      (node (ref "C14") (pin "1") (pinfunction "1_1") (pintype "input"))
      (node (ref "R10") (pin "1") (pinfunction "1_1") (pintype "input"))
      (node (ref "R8") (pin "1") (pinfunction "1_1") (pintype "input"))
      (node (ref "U11") (pin "2") (pinfunction "IN1-_2") (pintype "unspecified"))
    )
    (net (code "37") (name "Net-(U11A-OUT1)") (class "Default")
      (node (ref "C14") (pin "2") (pinfunction "2_2") (pintype "input"))
      (node (ref "R4") (pin "2") (pinfunction "2_2") (pintype "input"))
      (node (ref "R8") (pin "2") (pinfunction "2_2") (pintype "input"))
      (node (ref "U11") (pin "1") (pinfunction "OUT1_1") (pintype "unspecified"))
    )
    (net (code "38") (name "Net-(U11B-IN2-)") (class "Default")
      (node (ref "C16") (pin "2") (pinfunction "2_2") (pintype "input"))
      (node (ref "R10") (pin "2") (pinfunction "2_2") (pintype "input"))
      (node (ref "R10") (pin "3") (pinfunction "3_3") (pintype "input"))
      (node (ref "R11") (pin "2") (pinfunction "2_2") (pintype "input"))
      (node (ref "U11") (pin "6") (pinfunction "IN2-_6") (pintype "unspecified"))
    )
    (net (code "39") (name "Net-(U11B-OUT2)") (class "Default")
      (node (ref "C16") (pin "1") (pinfunction "1_1") (pintype "input"))
      (node (ref "R11") (pin "1") (pinfunction "1_1") (pintype "input"))
      (node (ref "R12") (pin "2") (pinfunction "2_2") (pintype "input"))
      (node (ref "U11") (pin "7") (pinfunction "OUT2_7") (pintype "unspecified"))
    )
    (net (code "40") (name "Net-(U11C-IN3+)") (class "Default")
      (node (ref "R12") (pin "1") (pinfunction "1_1") (pintype "input"))
      (node (ref "R13") (pin "2") (pinfunction "2_2") (pintype "input"))
      (node (ref "U11") (pin "10") (pinfunction "IN3+_10") (pintype "unspecified"))
    )
    (net (code "41") (name "Net-(U11C-IN3-)") (class "Default")
      (node (ref "R4") (pin "1") (pinfunction "1_1") (pintype "input"))
      (node (ref "R5") (pin "2") (pinfunction "2_2") (pintype "input"))
      (node (ref "U11") (pin "9") (pinfunction "IN3-_9") (pintype "unspecified"))
    )
    (net (code "42") (name "Net-(U11D-IN4+)") (class "Default")
      (node (ref "R6") (pin "1") (pinfunction "1_1") (pintype "input"))
      (node (ref "R7") (pin "1") (pinfunction "1_1") (pintype "input"))
      (node (ref "U11") (pin "12") (pinfunction "IN4+_12") (pintype "unspecified"))
    )
    (net (code "43") (name "P12") (class "Default")
      (node (ref "R19") (pin "1") (pinfunction "1_1") (pintype "input"))
      (node (ref "U10") (pin "5") (pinfunction "ECI/SS/ADC2/P1.2_5") (pintype "input"))
      (node (ref "U6") (pin "2") (pinfunction "#RE_2") (pintype "unspecified"))
      (node (ref "U6") (pin "3") (pinfunction "DE_3") (pintype "unspecified"))
    )
    (net (code "44") (name "P20") (class "Default")
      (node (ref "C18") (pin "2") (pinfunction "2_2") (pintype "input"))
      (node (ref "R23") (pin "2") (pinfunction "2_2") (pintype "input"))
      (node (ref "U10") (pin "23") (pinfunction "P2.0/RSTOUT_LOW_23") (pintype "input"))
      (node (ref "U7") (pin "1") (pinfunction "G_1") (pintype "unspecified"))
    )
    (net (code "45") (name "P21") (class "Default")
      (node (ref "CN5") (pin "5") (pinfunction "5_5") (pintype "unspecified"))
      (node (ref "U10") (pin "24") (pinfunction "P2.1/SCLK_2_24") (pintype "input"))
    )
    (net (code "46") (name "P22") (class "Default")
      (node (ref "CN5") (pin "4") (pinfunction "4_4") (pintype "unspecified"))
      (node (ref "U10") (pin "25") (pinfunction "P2.2/MISO_2_25") (pintype "input"))
    )
    (net (code "47") (name "P23") (class "Default")
      (node (ref "CN5") (pin "3") (pinfunction "3_3") (pintype "unspecified"))
      (node (ref "U10") (pin "26") (pinfunction "P2.3/MOSI_2_26") (pintype "input"))
    )
    (net (code "48") (name "P24") (class "Default")
      (node (ref "CN5") (pin "2") (pinfunction "2_2") (pintype "unspecified"))
      (node (ref "U10") (pin "27") (pinfunction "P2.4/ECI_3/SS_2_27") (pintype "input"))
    )
    (net (code "49") (name "P25") (class "Default")
      (node (ref "C17") (pin "2") (pinfunction "2_2") (pintype "input"))
      (node (ref "R17") (pin "2") (pinfunction "2_2") (pintype "input"))
      (node (ref "U10") (pin "28") (pinfunction "P2.5/CCP0_3_28") (pintype "input"))
      (node (ref "U5") (pin "1") (pinfunction "G_1") (pintype "unspecified"))
    )
    (net (code "50") (name "P36") (class "Default")
      (node (ref "R26") (pin "1") (pinfunction "1_1") (pintype "input"))
      (node (ref "U10") (pin "21") (pinfunction "P3.6/INT2#/RxD_2/CCP1_2_21") (pintype "input"))
    )
    (net (code "51") (name "P37") (class "Default")
      (node (ref "R15") (pin "1") (pinfunction "1_1") (pintype "input"))
      (node (ref "U10") (pin "22") (pinfunction "P3.7/INT3#/TxD_2/CCP2/CCP2_2_22") (pintype "input"))
    )
    (net (code "52") (name "SCL") (class "Default")
      (node (ref "R29") (pin "2") (pinfunction "2_2") (pintype "input"))
      (node (ref "U10") (pin "2") (pinfunction "CCP2_3/P2.7_2") (pintype "input"))
      (node (ref "U9") (pin "6") (pinfunction "SCL_6") (pintype "unspecified"))
    )
    (net (code "53") (name "SDA") (class "Default")
      (node (ref "R28") (pin "2") (pinfunction "2_2") (pintype "input"))
      (node (ref "U10") (pin "1") (pinfunction "CCP1_3/P2.6_1") (pintype "input"))
      (node (ref "U9") (pin "5") (pinfunction "SDA_5") (pintype "unspecified"))
    )
    (net (code "54") (name "SN+") (class "Default")
      (node (ref "CN4") (pin "2") (pinfunction "2_2") (pintype "unspecified"))
      (node (ref "U11") (pin "3") (pinfunction "IN1+_3") (pintype "unspecified"))
    )
    (net (code "55") (name "SN-") (class "Default")
      (node (ref "CN4") (pin "1") (pinfunction "1_1") (pintype "unspecified"))
      (node (ref "U11") (pin "5") (pinfunction "IN2+_5") (pintype "unspecified"))
    )
    (net (code "56") (name "VBAT") (class "Default")
      (node (ref "C1") (pin "1") (pinfunction "1_1") (pintype "input"))
      (node (ref "CN4") (pin "4") (pinfunction "4_4") (pintype "unspecified"))
      (node (ref "R6") (pin "2") (pinfunction "2_2") (pintype "input"))
      (node (ref "SW1") (pin "2") (pinfunction "2_2") (pintype "unspecified"))
      (node (ref "U1") (pin "1") (pinfunction "VIN_1") (pintype "input"))
    )
    (net (code "57") (name "VCC") (class "Default")
      (node (ref "C11") (pin "2") (pinfunction "2_2") (pintype "unspecified"))
      (node (ref "C12") (pin "2") (pinfunction "2_2") (pintype "input"))
      (node (ref "C15") (pin "1") (pinfunction "1_1") (pintype "input"))
      (node (ref "C17") (pin "1") (pinfunction "1_1") (pintype "input"))
      (node (ref "C18") (pin "1") (pinfunction "1_1") (pintype "input"))
      (node (ref "C2") (pin "2") (pinfunction "2_2") (pintype "input"))
      (node (ref "C20") (pin "2") (pinfunction "2_2") (pintype "input"))
      (node (ref "C21") (pin "1") (pinfunction "1_1") (pintype "input"))
      (node (ref "C23") (pin "2") (pinfunction "2_2") (pintype "input"))
      (node (ref "C3") (pin "2") (pinfunction "2_2") (pintype "input"))
      (node (ref "C4") (pin "1") (pinfunction "1_1") (pintype "input"))
      (node (ref "C5") (pin "1") (pinfunction "1_1") (pintype "unspecified"))
      (node (ref "C6") (pin "1") (pinfunction "1_1") (pintype "unspecified"))
      (node (ref "CN5") (pin "7") (pinfunction "7_7") (pintype "unspecified"))
      (node (ref "D1") (pin "1") (pinfunction "C_1") (pintype "unspecified"))
      (node (ref "H1") (pin "3") (pinfunction "3_3") (pintype "unspecified"))
      (node (ref "L1") (pin "1") (pinfunction "1_1") (pintype "unspecified"))
      (node (ref "LED1") (pin "1") (pinfunction "C_1") (pintype "input"))
      (node (ref "R17") (pin "1") (pinfunction "1_1") (pintype "input"))
      (node (ref "R18") (pin "2") (pinfunction "2_2") (pintype "input"))
      (node (ref "R21") (pin "2") (pinfunction "2_2") (pintype "input"))
      (node (ref "R23") (pin "1") (pinfunction "1_1") (pintype "input"))
      (node (ref "R3") (pin "1") (pinfunction "1_1") (pintype "input"))
      (node (ref "U1") (pin "4") (pinfunction "FEEDBACK_4") (pintype "input"))
      (node (ref "U10") (pin "12") (pinfunction "Vcc_12") (pintype "input"))
      (node (ref "U11") (pin "4") (pinfunction "VCC+_4") (pintype "unspecified"))
      (node (ref "U2") (pin "2") (pinfunction "VIN_2") (pintype "input"))
      (node (ref "U3") (pin "2") (pinfunction "IN_2") (pintype "unspecified"))
      (node (ref "U4") (pin "1") (pinfunction "1_1") (pintype "input"))
      (node (ref "U5") (pin "2") (pinfunction "S_2") (pintype "unspecified"))
      (node (ref "U6") (pin "8") (pinfunction "VCC_8") (pintype "unspecified"))
      (node (ref "U7") (pin "2") (pinfunction "S_2") (pintype "unspecified"))
      (node (ref "U8") (pin "1") (pinfunction "1_1") (pintype "input"))
      (node (ref "U9") (pin "1") (pinfunction "A0_1") (pintype "unspecified"))
      (node (ref "U9") (pin "8") (pinfunction "VCC_8") (pintype "unspecified"))
    )
    (net (code "58") (name "VEE") (class "Default")
      (node (ref "C13") (pin "2") (pinfunction "2_2") (pintype "input"))
      (node (ref "C8") (pin "2") (pinfunction "2_2") (pintype "unspecified"))
      (node (ref "U11") (pin "11") (pinfunction "VCC-_11") (pintype "unspecified"))
      (node (ref "U3") (pin "1") (pinfunction "OUT_1") (pintype "unspecified"))
    )
    (net (code "59") (name "VRM") (class "Default")
      (node (ref "C10") (pin "2") (pinfunction "2_2") (pintype "input"))
      (node (ref "C9") (pin "2") (pinfunction "2_2") (pintype "unspecified"))
      (node (ref "D3") (pin "1") (pinfunction "C_1") (pintype "unspecified"))
      (node (ref "D5") (pin "1") (pinfunction "C_1") (pintype "unspecified"))
      (node (ref "R14") (pin "1") (pinfunction "1_1") (pintype "input"))
      (node (ref "R2") (pin "2") (pinfunction "2_2") (pintype "input"))
      (node (ref "R24") (pin "2") (pinfunction "2_2") (pintype "input"))
      (node (ref "R25") (pin "1") (pinfunction "1_1") (pintype "input"))
      (node (ref "R9") (pin "2") (pinfunction "2_2") (pintype "input"))
      (node (ref "RELAY1") (pin "2") (pinfunction "2_2") (pintype "input"))
      (node (ref "RELAY2") (pin "2") (pinfunction "2_2") (pintype "input"))
      (node (ref "U2") (pin "4") (pinfunction "+Vo_4") (pintype "input"))
    )
    (net (code "60") (name "XTAL1") (class "Default")
      (node (ref "C19") (pin "1") (pinfunction "1_1") (pintype "input"))
      (node (ref "U10") (pin "10") (pinfunction "XTAL1/TxD_3/ADC7/P1.7_10") (pintype "input"))
      (node (ref "X1") (pin "2") (pinfunction "2_2") (pintype "unspecified"))
    )
    (net (code "61") (name "XTAL2") (class "Default")
      (node (ref "C22") (pin "1") (pinfunction "1_1") (pintype "input"))
      (node (ref "U10") (pin "9") (pinfunction "XTAL2/RxD_3/ADC6/P1.6_9") (pintype "input"))
      (node (ref "X1") (pin "1") (pinfunction "1_1") (pintype "unspecified"))
    )
    (net (code "62") (name "unconnected-(SW1-Pad3)") (class "Default")
      (node (ref "SW1") (pin "3") (pinfunction "3_3") (pintype "unspecified+no_connect"))
    )
    (net (code "63") (name "unconnected-(SW1-Pad4)") (class "Default")
      (node (ref "SW1") (pin "4") (pinfunction "4_4") (pintype "unspecified+no_connect"))
    )
    (net (code "64") (name "unconnected-(SW1-Pad5)") (class "Default")
      (node (ref "SW1") (pin "5") (pinfunction "5_5") (pintype "unspecified+no_connect"))
    )
    (net (code "65") (name "unconnected-(U10-MCLKO{slash}RST{slash}P5.4-Pad11)") (class "Default")
      (node (ref "U10") (pin "11") (pinfunction "MCLKO/RST/P5.4_11") (pintype "input+no_connect"))
    )
    (net (code "66") (name "unconnected-(U10-P3.2{slash}INT0-Pad17)") (class "Default")
      (node (ref "U10") (pin "17") (pinfunction "P3.2/INT0_17") (pintype "input+no_connect"))
    )
    (net (code "67") (name "unconnected-(U10-P3.3{slash}INT1-Pad18)") (class "Default")
      (node (ref "U10") (pin "18") (pinfunction "P3.3/INT1_18") (pintype "input+no_connect"))
    )
    (net (code "68") (name "unconnected-(U10-P3.4{slash}T0{slash}T1CLKO{slash}ECI_2-Pad19)") (class "Default")
      (node (ref "U10") (pin "19") (pinfunction "P3.4/T0/T1CLKO/ECI_2_19") (pintype "input+no_connect"))
    )
    (net (code "69") (name "unconnected-(U10-P3.5{slash}T1{slash}T0CLKO{slash}CCP0_2-Pad20)") (class "Default")
      (node (ref "U10") (pin "20") (pinfunction "P3.5/T1/T0CLKO/CCP0_2_20") (pintype "input+no_connect"))
    )
    (net (code "70") (name "unconnected-(U10-P5.5-Pad13)") (class "Default")
      (node (ref "U10") (pin "13") (pinfunction "P5.5_13") (pintype "input+no_connect"))
    )
    (net (code "71") (name "unconnected-(U10-SCLK{slash}ADC5{slash}P1.5-Pad8)") (class "Default")
      (node (ref "U10") (pin "8") (pinfunction "SCLK/ADC5/P1.5_8") (pintype "input+no_connect"))
    )
  )
)
